# tricorder-light-sensors-mk-1_0.net
KiCad netlist of a schematic drawn in EAGLE
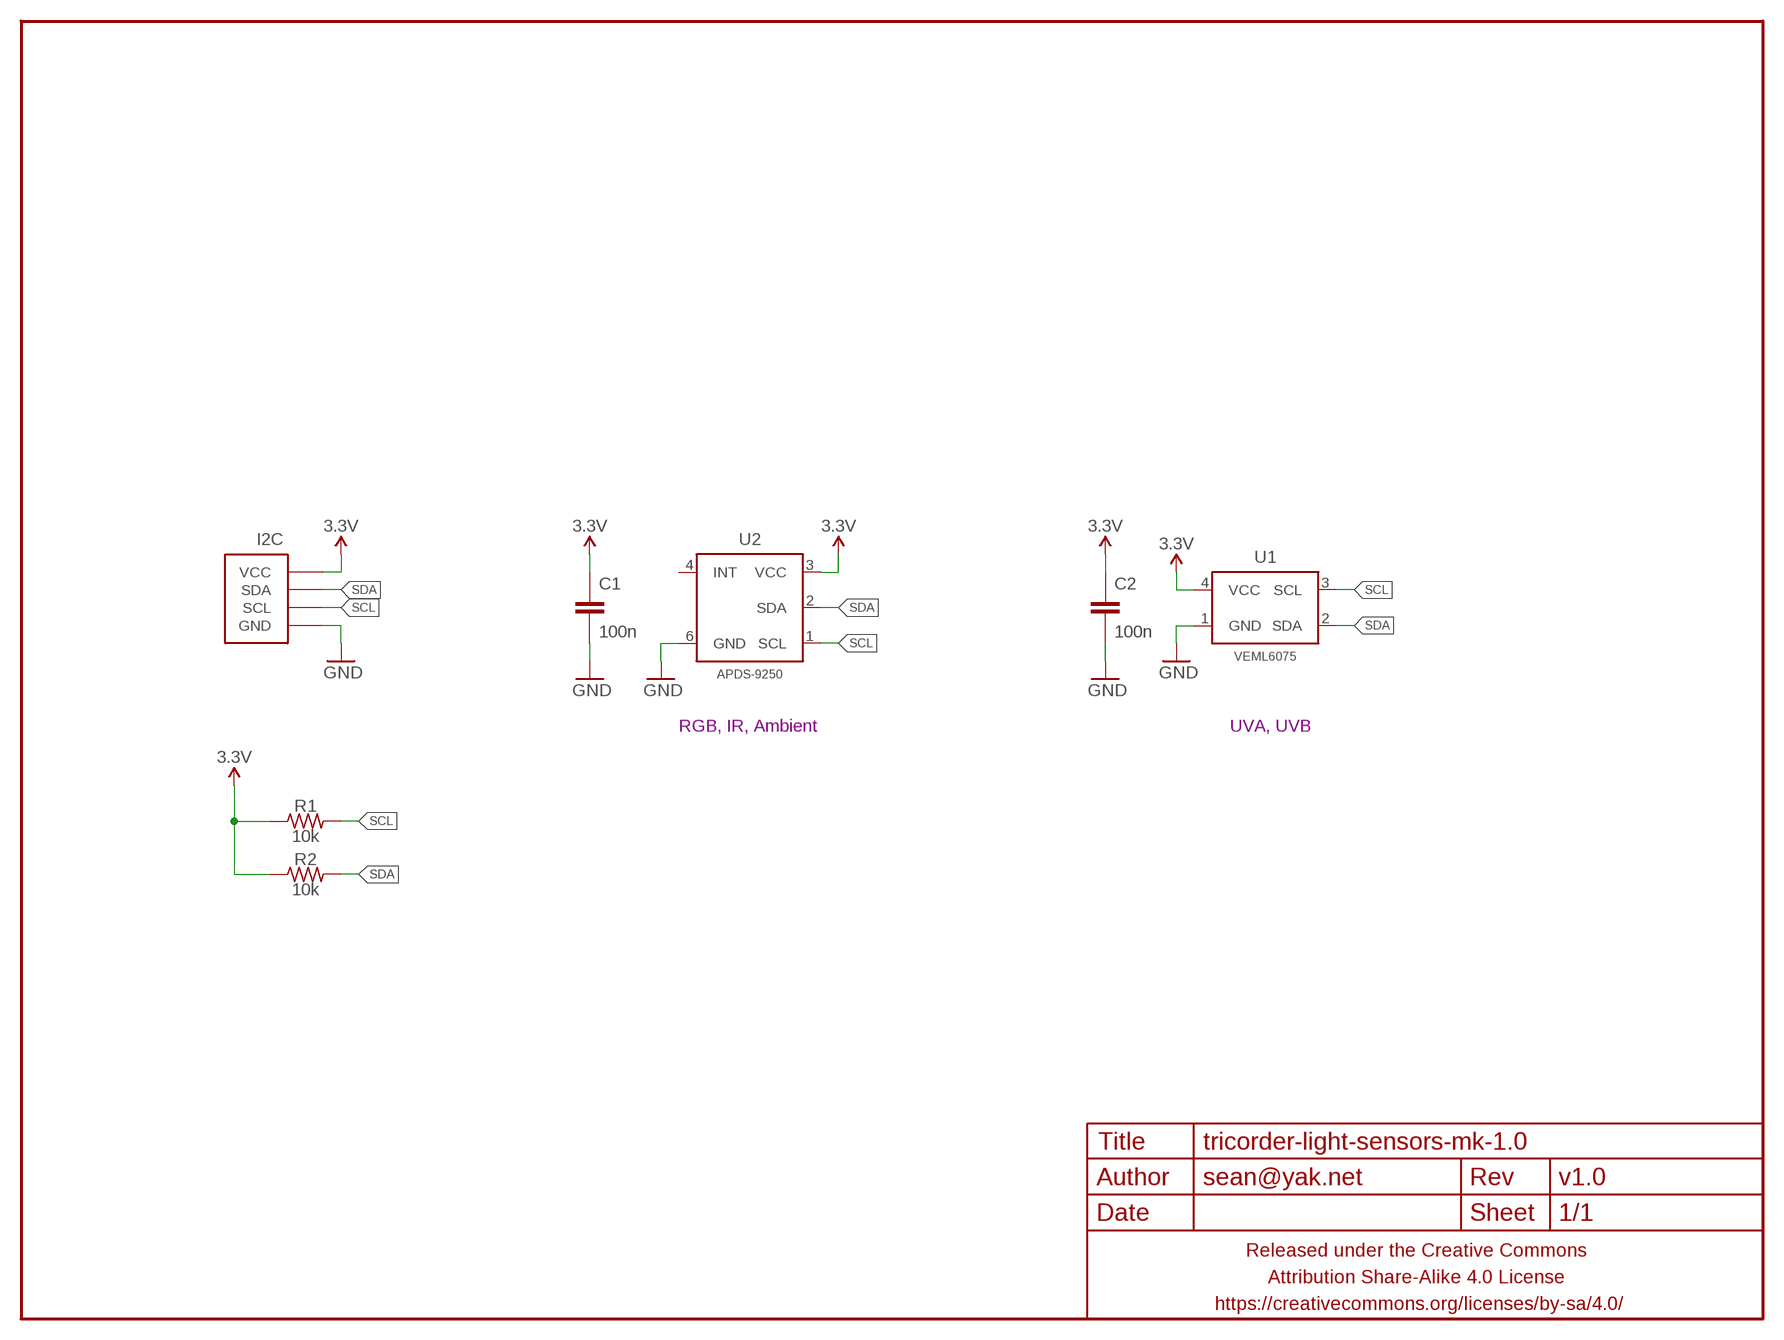
[diagram p0: schematic, sheet 1]

(export (version "E")
  (design (tool "Eeschema 10.0.6"))
  (components
    (comp (ref "C1")
      (value "100n")
      (footprint "eagle-import:C0603")
      (libsource (lib "eagle-import") (part "CAPACITOR-CERAMICC0603"))
    )
    (comp (ref "C2")
      (value "100n")
      (footprint "eagle-import:C0603")
      (libsource (lib "eagle-import") (part "CAPACITOR-CERAMICC0603"))
    )
    (comp (ref "FRAME1")
      (value "FRAME-LETTERNO_PACKAGE")
      (footprint "eagle-import:DUMMY")
      (fields (field (name "DESIGNER") "sean@yak.net") (field (name "VERSION") "v1.0"))
      (libsource (lib "eagle-import") (part "FRAME-LETTERNO_PACKAGE"))
    )
    (comp (ref "I2C")
      (value "M04-I2CPTH-0.1IN-CENTERED")
      (footprint "eagle-import:1X04-PTH-VERT-I2C-CENTERED")
      (libsource (lib "eagle-import") (part "M04-I2CPTH-0.1IN-CENTERED"))
    )
    (comp (ref "R1")
      (value "10k")
      (footprint "eagle-import:R0603")
      (libsource (lib "eagle-import") (part "RESISTORR0603"))
    )
    (comp (ref "R2")
      (value "10k")
      (footprint "eagle-import:R0603")
      (libsource (lib "eagle-import") (part "RESISTORR0603"))
    )
    (comp (ref "U1")
      (value "VEML6075")
      (footprint "eagle-import:OPLGA4")
      (libsource (lib "eagle-import") (part "VEML6075"))
    )
    (comp (ref "U2")
      (value "APDS-9250")
      (footprint "eagle-import:APDS-9250-ALT")
      (libsource (lib "eagle-import") (part "APDS-9250ALT"))
    )
  )
  (nets
    (net (code "1") (name "3.3V") (class "Default")
      (node (ref "C1") (pin "1") (pinfunction "1_1") (pintype "passive"))
      (node (ref "C2") (pin "1") (pinfunction "1_1") (pintype "passive"))
      (node (ref "I2C") (pin "VCC") (pinfunction "VCC_VCC") (pintype "bidirectional"))
      (node (ref "R1") (pin "1") (pinfunction "1_1") (pintype "passive"))
      (node (ref "R2") (pin "1") (pinfunction "1_1") (pintype "passive"))
      (node (ref "U1") (pin "4") (pinfunction "VCC_4") (pintype "bidirectional"))
      (node (ref "U2") (pin "3") (pinfunction "VCC_3") (pintype "bidirectional"))
    )
    (net (code "2") (name "GND") (class "Default")
      (node (ref "C1") (pin "2") (pinfunction "2_2") (pintype "passive"))
      (node (ref "C2") (pin "2") (pinfunction "2_2") (pintype "passive"))
      (node (ref "I2C") (pin "GND") (pinfunction "GND_GND") (pintype "bidirectional"))
      (node (ref "U1") (pin "1") (pinfunction "GND_1") (pintype "bidirectional"))
      (node (ref "U2") (pin "6") (pinfunction "GND_6") (pintype "bidirectional"))
    )
    (net (code "3") (name "SCL") (class "Default")
      (node (ref "I2C") (pin "SCL") (pinfunction "SCL_SCL") (pintype "bidirectional"))
      (node (ref "R1") (pin "2") (pinfunction "2_2") (pintype "passive"))
      (node (ref "U1") (pin "3") (pinfunction "SCL_3") (pintype "bidirectional"))
      (node (ref "U2") (pin "1") (pinfunction "SCL_1") (pintype "bidirectional"))
    )
    (net (code "4") (name "SDA") (class "Default")
      (node (ref "I2C") (pin "SDA") (pinfunction "SDA_SDA") (pintype "bidirectional"))
      (node (ref "R2") (pin "2") (pinfunction "2_2") (pintype "passive"))
      (node (ref "U1") (pin "2") (pinfunction "SDA_2") (pintype "bidirectional"))
      (node (ref "U2") (pin "2") (pinfunction "SDA_2") (pintype "bidirectional"))
    )
    (net (code "5") (name "unconnected-(U2-INT-Pad4)") (class "Default")
      (node (ref "U2") (pin "4") (pinfunction "INT_4") (pintype "bidirectional"))
    )
  )
)
